# 14_-MAIN_CONNECTORS.net
KiCad netlist of a schematic drawn in Altium Designer
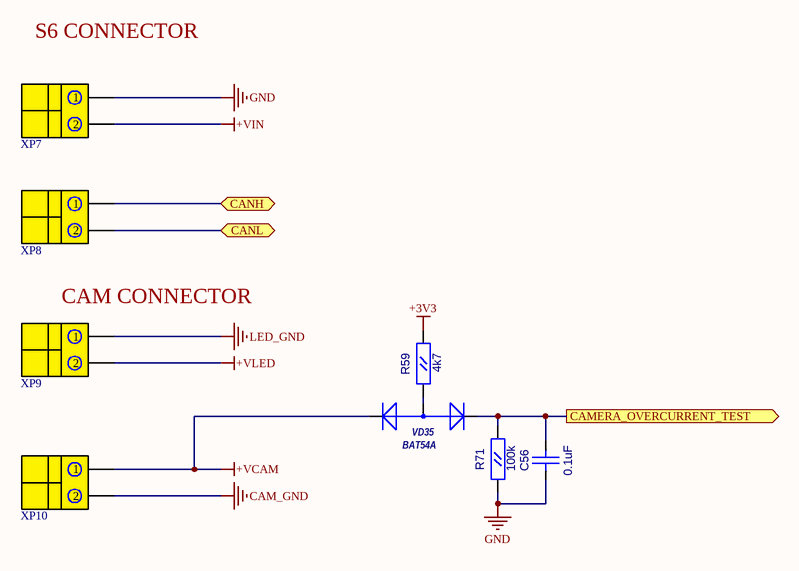
[diagram p0: [14]-MAIN_CONNECTORS.SchDoc]

(export (version "E")
  (design (tool "Eeschema 10.0.6"))
  (components
    (comp (ref "C56")
      (value "0.1uF")
      (footprint "CC0603")
      (description "CC0603")
      (libsource (lib "fizik_lib") (part "CC0603"))
    )
    (comp (ref "R59")
      (value "4k7")
      (footprint "RC0603")
      (description "RC0603")
      (libsource (lib "fizik_lib") (part "RC0603"))
    )
    (comp (ref "R71")
      (value "100k")
      (footprint "RC0603")
      (description "RC0603")
      (libsource (lib "fizik_lib") (part "RC0603"))
    )
    (comp (ref "VD35")
      (value "BAT54A")
      (footprint "SOT-23(123)")
      (description "1.0 Ampere General Purpose Rectifier")
      (libsource (lib "fizik_lib") (part "BAT54A"))
    )
    (comp (ref "XP7")
      (value "DG330-2P")
      (footprint "DG330-2P")
      (description "Degson 2 pin connector rear")
      (libsource (lib "fizik_lib") (part "DG330-2P"))
    )
    (comp (ref "XP8")
      (value "DG330-2P")
      (footprint "DG330-2P")
      (description "Degson 2 pin connector rear")
      (libsource (lib "fizik_lib") (part "DG330-2P"))
    )
    (comp (ref "XP9")
      (value "DG330-2P")
      (footprint "DG330-2P")
      (description "Degson 2 pin connector rear")
      (libsource (lib "fizik_lib") (part "DG330-2P"))
    )
    (comp (ref "XP10")
      (value "DG330-2P")
      (footprint "DG330-2P")
      (description "Degson 2 pin connector rear")
      (libsource (lib "fizik_lib") (part "DG330-2P"))
    )
  )
  (nets
    (net (code "1") (name "+3V3") (class "Default")
      (node (ref "R59") (pin "2") (pinfunction "B_2") (pintype "passive"))
    )
    (net (code "2") (name "+VCAM") (class "Default")
      (node (ref "VD35") (pin "1") (pinfunction "K_1") (pintype "passive"))
      (node (ref "XP10") (pin "1") (pinfunction "1_1") (pintype "passive"))
    )
    (net (code "3") (name "+VIN") (class "Default")
      (node (ref "XP7") (pin "2") (pinfunction "2_2") (pintype "passive"))
    )
    (net (code "4") (name "+VLED") (class "Default")
      (node (ref "XP9") (pin "2") (pinfunction "2_2") (pintype "passive"))
    )
    (net (code "5") (name "/CAMERA_OVERCURRENT_TEST") (class "Default")
      (node (ref "C56") (pin "2") (pinfunction "B_2") (pintype "passive"))
      (node (ref "R71") (pin "2") (pinfunction "B_2") (pintype "passive"))
      (node (ref "VD35") (pin "2") (pinfunction "K_2") (pintype "passive"))
    )
    (net (code "6") (name "/CANH") (class "Default")
      (node (ref "XP8") (pin "1") (pinfunction "1_1") (pintype "passive"))
    )
    (net (code "7") (name "/CANL") (class "Default")
      (node (ref "XP8") (pin "2") (pinfunction "2_2") (pintype "passive"))
    )
    (net (code "8") (name "CAM_GND") (class "Default")
      (node (ref "XP10") (pin "2") (pinfunction "2_2") (pintype "passive"))
    )
    (net (code "9") (name "GND") (class "Default")
      (node (ref "C56") (pin "1") (pinfunction "A_1") (pintype "passive"))
      (node (ref "R71") (pin "1") (pinfunction "A_1") (pintype "passive"))
      (node (ref "XP7") (pin "1") (pinfunction "1_1") (pintype "passive"))
    )
    (net (code "10") (name "LED_GND") (class "Default")
      (node (ref "XP9") (pin "1") (pinfunction "1_1") (pintype "passive"))
    )
    (net (code "11") (name "Net-(R59-A)") (class "Default")
      (node (ref "R59") (pin "1") (pinfunction "A_1") (pintype "passive"))
      (node (ref "VD35") (pin "3") (pinfunction "A_3") (pintype "passive"))
    )
  )
)
